# Sensor_Module.net
KiCad netlist of a schematic drawn in Altium Designer
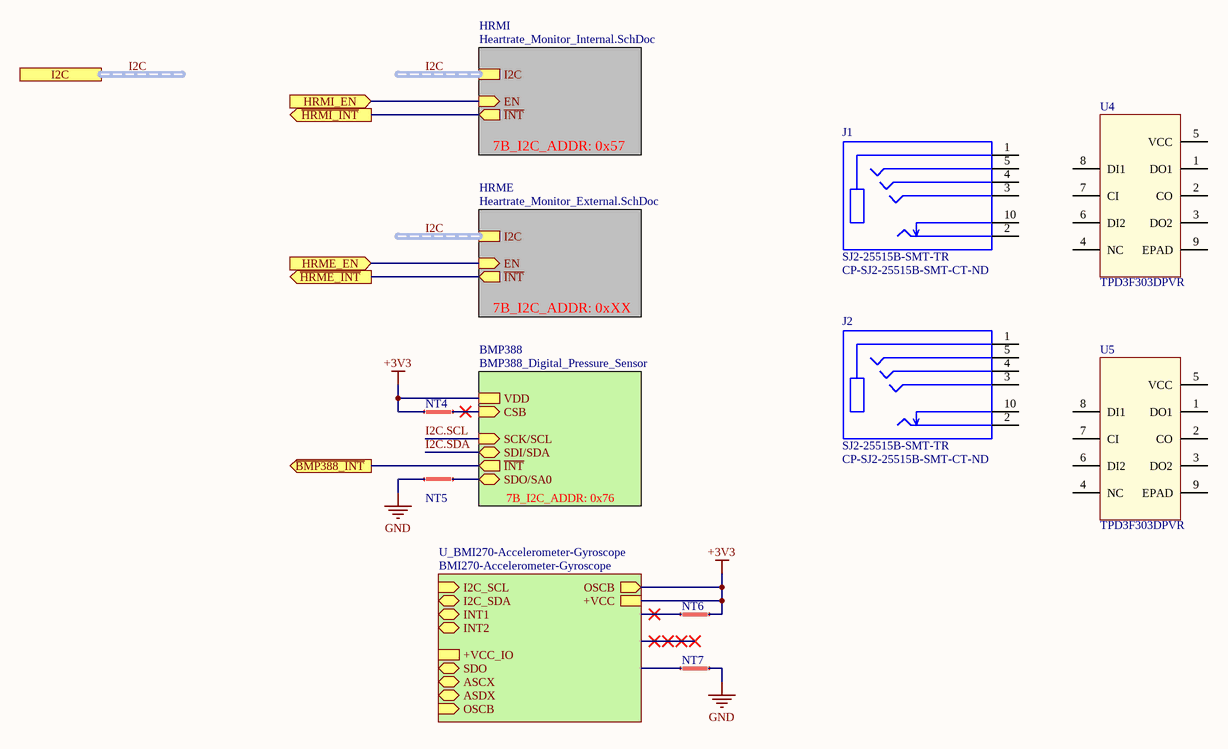
[diagram p0: Sensor_Module.SchDoc]

(export (version "E")
  (design (tool "Eeschema 10.0.6"))
  (components
    (comp (ref "J1")
      (value "SJ2-25515B-SMT-TR")
      (footprint "CUI_SJ2-25515B-SMT-TR")
      (description "5 conductor, 2.5 mm, SMT Audio Jack w/ Tip Switch")
      (fields
        (field (name "MF") "CUI")
        (field (name "SUPPLIER PART NUMBER 1") "CP-SJ2-25515B-SMT-CT-ND")
        (field (name "CONTACT") "5(Excludes TIP Switch)")
      )
      (libsource (lib "SJ2-25515B-SMT-TR") (part "SJ2-25515B-SMT-TR"))
    )
    (comp (ref "J2")
      (value "SJ2-25515B-SMT-TR")
      (footprint "CUI_SJ2-25515B-SMT-TR")
      (description "5 conductor, 2.5 mm, SMT Audio Jack w/ Tip Switch")
      (fields
        (field (name "MF") "CUI")
        (field (name "SUPPLIER PART NUMBER 1") "CP-SJ2-25515B-SMT-CT-ND")
        (field (name "CONTACT") "5(Excludes TIP Switch)")
      )
      (libsource (lib "SJ2-25515B-SMT-TR") (part "SJ2-25515B-SMT-TR"))
    )
    (comp (ref "NT4")
      (value "Net Tie")
      (footprint "Net Tie 6x30mil")
      (libsource (lib "") (part "Net Tie Line_1"))
    )
    (comp (ref "NT5")
      (value "Net Tie")
      (footprint "Net Tie 6x30mil")
      (libsource (lib "BLDC_Motor_Driver") (part "Net Tie Line"))
    )
    (comp (ref "NT6")
      (value "Net Tie")
      (footprint "Net Tie 6x30mil")
      (libsource (lib "") (part "Net Tie Line_1"))
    )
    (comp (ref "NT7")
      (value "Net Tie")
      (footprint "Net Tie 6x30mil")
      (libsource (lib "") (part "Net Tie Line_1"))
    )
    (comp (ref "U4")
      (value "TPD3F303DPVR")
      (footprint "DPV8_1P7X0P4")
      (description "RC (Pi) EMI Filter 2nd Order Low Pass 3 Channel R = 47Ohms, 100Ohms, C = 20pF  8-UFDFN Exposed Pad")
      (fields (field (name "MANUFACTURER") "Texas Instruments"))
      (libsource (lib "Control_Board_Model_C201") (part "FILTER RC(PI) ESD SMD  8-UFDFN EP"))
    )
    (comp (ref "U5")
      (value "TPD3F303DPVR")
      (footprint "DPV8_1P7X0P4")
      (description "RC (Pi) EMI Filter 2nd Order Low Pass 3 Channel R = 47Ohms, 100Ohms, C = 20pF  8-UFDFN Exposed Pad")
      (fields (field (name "MANUFACTURER") "Texas Instruments"))
      (libsource (lib "Control_Board_Model_C201") (part "FILTER RC(PI) ESD SMD  8-UFDFN EP"))
    )
  )
  (nets
    (net (code "2") (name "+3V3") (class "Default")
      (node (ref "NT4") (pin "1") (pintype "passive"))
      (node (ref "NT6") (pin "2") (pintype "passive"))
    )
    (net (code "7") (name "/CSB") (class "Default") (node (ref "NT4") (pin "2") (pintype "passive")))
    (net (code "20") (name "/SDO{slash}SA0") (class "Default")
      (node (ref "NT5") (pin "1") (pintype "passive"))
    )
    (net (code "22") (name "GND") (class "Default")
      (node (ref "NT5") (pin "2") (pintype "passive"))
      (node (ref "NT7") (pin "2") (pintype "passive"))
    )
    (net (code "23") (name "unconnected-(J1-OUTER_RING-Pad1)") (class "Default")
      (node (ref "J1") (pin "1") (pinfunction "OUTER_RING_1") (pintype "passive"))
    )
    (net (code "24") (name "unconnected-(J1-RING1-Pad3)") (class "Default")
      (node (ref "J1") (pin "3") (pinfunction "RING1_3") (pintype "passive"))
    )
    (net (code "25") (name "unconnected-(J1-RING2-Pad4)") (class "Default")
      (node (ref "J1") (pin "4") (pinfunction "RING2_4") (pintype "passive"))
    )
    (net (code "26") (name "unconnected-(J1-SLEEVE-Pad5)") (class "Default")
      (node (ref "J1") (pin "5") (pinfunction "SLEEVE_5") (pintype "passive"))
    )
    (net (code "27") (name "unconnected-(J1-TIP-Pad2)") (class "Default")
      (node (ref "J1") (pin "2") (pinfunction "TIP_2") (pintype "passive"))
    )
    (net (code "28") (name "unconnected-(J1-TIP_SWITCH-Pad10)") (class "Default")
      (node (ref "J1") (pin "10") (pinfunction "TIP_SWITCH_10") (pintype "passive"))
    )
    (net (code "29") (name "unconnected-(J2-OUTER_RING-Pad1)") (class "Default")
      (node (ref "J2") (pin "1") (pinfunction "OUTER_RING_1") (pintype "passive"))
    )
    (net (code "30") (name "unconnected-(J2-RING1-Pad3)") (class "Default")
      (node (ref "J2") (pin "3") (pinfunction "RING1_3") (pintype "passive"))
    )
    (net (code "31") (name "unconnected-(J2-RING2-Pad4)") (class "Default")
      (node (ref "J2") (pin "4") (pinfunction "RING2_4") (pintype "passive"))
    )
    (net (code "32") (name "unconnected-(J2-SLEEVE-Pad5)") (class "Default")
      (node (ref "J2") (pin "5") (pinfunction "SLEEVE_5") (pintype "passive"))
    )
    (net (code "33") (name "unconnected-(J2-TIP-Pad2)") (class "Default")
      (node (ref "J2") (pin "2") (pinfunction "TIP_2") (pintype "passive"))
    )
    (net (code "34") (name "unconnected-(J2-TIP_SWITCH-Pad10)") (class "Default")
      (node (ref "J2") (pin "10") (pinfunction "TIP_SWITCH_10") (pintype "passive"))
    )
    (net (code "35") (name "unconnected-(NT6-Pad1)") (class "Default")
      (node (ref "NT6") (pin "1") (pintype "passive"))
    )
    (net (code "36") (name "unconnected-(NT7-Pad1)") (class "Default")
      (node (ref "NT7") (pin "1") (pintype "passive"))
    )
    (net (code "37") (name "unconnected-(U4-CI-Pad7)") (class "Default")
      (node (ref "U4") (pin "7") (pinfunction "CI_7") (pintype "passive"))
    )
    (net (code "38") (name "unconnected-(U4-CO-Pad2)") (class "Default")
      (node (ref "U4") (pin "2") (pinfunction "CO_2") (pintype "passive"))
    )
    (net (code "39") (name "unconnected-(U4-DI1-Pad8)") (class "Default")
      (node (ref "U4") (pin "8") (pinfunction "DI1_8") (pintype "passive"))
    )
    (net (code "40") (name "unconnected-(U4-DI2-Pad6)") (class "Default")
      (node (ref "U4") (pin "6") (pinfunction "DI2_6") (pintype "passive"))
    )
    (net (code "41") (name "unconnected-(U4-DO1-Pad1)") (class "Default")
      (node (ref "U4") (pin "1") (pinfunction "DO1_1") (pintype "passive"))
    )
    (net (code "42") (name "unconnected-(U4-DO2-Pad3)") (class "Default")
      (node (ref "U4") (pin "3") (pinfunction "DO2_3") (pintype "passive"))
    )
    (net (code "43") (name "unconnected-(U4-EPAD-Pad9)") (class "Default")
      (node (ref "U4") (pin "9") (pinfunction "EPAD_9") (pintype "passive"))
    )
    (net (code "44") (name "unconnected-(U4-NC-Pad4)") (class "Default")
      (node (ref "U4") (pin "4") (pinfunction "NC_4") (pintype "passive"))
    )
    (net (code "45") (name "unconnected-(U4-VCC-Pad5)") (class "Default")
      (node (ref "U4") (pin "5") (pinfunction "VCC_5") (pintype "power_in"))
    )
    (net (code "46") (name "unconnected-(U5-CI-Pad7)") (class "Default")
      (node (ref "U5") (pin "7") (pinfunction "CI_7") (pintype "passive"))
    )
    (net (code "47") (name "unconnected-(U5-CO-Pad2)") (class "Default")
      (node (ref "U5") (pin "2") (pinfunction "CO_2") (pintype "passive"))
    )
    (net (code "48") (name "unconnected-(U5-DI1-Pad8)") (class "Default")
      (node (ref "U5") (pin "8") (pinfunction "DI1_8") (pintype "passive"))
    )
    (net (code "49") (name "unconnected-(U5-DI2-Pad6)") (class "Default")
      (node (ref "U5") (pin "6") (pinfunction "DI2_6") (pintype "passive"))
    )
    (net (code "50") (name "unconnected-(U5-DO1-Pad1)") (class "Default")
      (node (ref "U5") (pin "1") (pinfunction "DO1_1") (pintype "passive"))
    )
    (net (code "51") (name "unconnected-(U5-DO2-Pad3)") (class "Default")
      (node (ref "U5") (pin "3") (pinfunction "DO2_3") (pintype "passive"))
    )
    (net (code "52") (name "unconnected-(U5-EPAD-Pad9)") (class "Default")
      (node (ref "U5") (pin "9") (pinfunction "EPAD_9") (pintype "passive"))
    )
    (net (code "53") (name "unconnected-(U5-NC-Pad4)") (class "Default")
      (node (ref "U5") (pin "4") (pinfunction "NC_4") (pintype "passive"))
    )
    (net (code "54") (name "unconnected-(U5-VCC-Pad5)") (class "Default")
      (node (ref "U5") (pin "5") (pinfunction "VCC_5") (pintype "power_in"))
    )
  )
)
